# CPS.net
KiCad netlist of a schematic drawn in Altium Designer
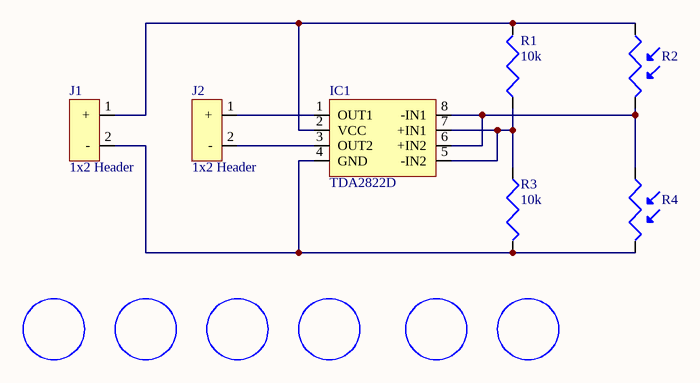
[diagram p0: CPS.SchDoc]

(export (version "E")
  (design (tool "Eeschema 10.0.6"))
  (components
    (comp (ref "H1") (value "Hole") (footprint "Hole") (libsource (lib "CPS") (part "Hole")))
    (comp (ref "H2") (value "Hole") (footprint "Hole") (libsource (lib "CPS") (part "Hole")))
    (comp (ref "H3") (value "Hole") (footprint "Hole") (libsource (lib "CPS") (part "Hole")))
    (comp (ref "H4") (value "Hole") (footprint "Hole") (libsource (lib "CPS") (part "Hole")))
    (comp (ref "H5") (value "Hole") (footprint "Hole") (libsource (lib "CPS") (part "Hole")))
    (comp (ref "H6") (value "Hole") (footprint "Hole") (libsource (lib "CPS") (part "Hole")))
    (comp (ref "IC1")
      (value "TDA2822D")
      (footprint "TDA2822D")
      (description "Audio Amp Headphone/Speaker 1-CH Mono/2-CH Stereo 1W Class-AB 8-Pin SO N Tube")
      (fields (field (name "MANUFACTURER") "STMicroelectronics"))
      (libsource (lib "CPS") (part "TDA2822D"))
    )
    (comp (ref "J1")
      (value "1x2 Header")
      (footprint "Conector")
      (description "KK 254 Wire-to-Board Header, Vertical, with Friction Lock, 2 Circuits, Gold (Au) Plating")
      (fields (field (name "MANUFACTURER") "Molex") (field (name "MANUFACTURER PART NUMBER") "22-29-2021"))
      (libsource (lib "CPS") (part "22-29-2021"))
    )
    (comp (ref "J2")
      (value "1x2 Header")
      (footprint "Conector")
      (description "KK 254 Wire-to-Board Header, Vertical, with Friction Lock, 2 Circuits, Gold (Au) Plating")
      (fields (field (name "MANUFACTURER") "Molex") (field (name "MANUFACTURER PART NUMBER") "22-29-2021"))
      (libsource (lib "CPS") (part "22-29-2021"))
    )
    (comp (ref "R1")
      (value "10k")
      (footprint "R0603")
      (description "SMD Chip Resistor, 10 kOhm, ± 1%, 100 mW, 0603 [1608 Metric], Thick Film, General Purpose")
      (fields
        (field (name "MANUFACTURER") "Vishay")
        (field (name "MANUFACTURER PART NUMBER") "CRCW060310K0FKEA")
      )
      (libsource (lib "CPS") (part "CRCW060310K0FKEA"))
    )
    (comp (ref "R2")
      (value "500k")
      (footprint "Photoresistor")
      (description "Ldr, 500 Kohm, 80MW, VT900 Series")
      (fields (field (name "MANUFACTURER") "Excelitas") (field (name "MANUFACTURER PART NUMBER") "VT90N2"))
      (libsource (lib "CPS") (part "VT90N2"))
    )
    (comp (ref "R3")
      (value "10k")
      (footprint "R0603")
      (description "SMD Chip Resistor, 10 kOhm, ± 1%, 100 mW, 0603 [1608 Metric], Thick Film, General Purpose")
      (fields
        (field (name "MANUFACTURER") "Vishay")
        (field (name "MANUFACTURER PART NUMBER") "CRCW060310K0FKEA")
      )
      (libsource (lib "CPS") (part "CRCW060310K0FKEA"))
    )
    (comp (ref "R4")
      (value "500k")
      (footprint "Photoresistor")
      (description "Ldr, 500 Kohm, 80MW, VT900 Series")
      (fields (field (name "MANUFACTURER") "Excelitas") (field (name "MANUFACTURER PART NUMBER") "VT90N2"))
      (libsource (lib "CPS") (part "VT90N2"))
    )
  )
  (nets
    (net (code "1") (name "Net-(IC1-+IN1)") (class "Default")
      (node (ref "IC1") (pin "5") (pinfunction "-IN2_5") (pintype "passive"))
      (node (ref "IC1") (pin "7") (pinfunction "+IN1_7") (pintype "passive"))
      (node (ref "R1") (pin "1") (pinfunction "1_1") (pintype "passive"))
      (node (ref "R3") (pin "1") (pinfunction "1_1") (pintype "passive"))
    )
    (net (code "2") (name "Net-(IC1-+IN2)") (class "Default")
      (node (ref "IC1") (pin "6") (pinfunction "+IN2_6") (pintype "passive"))
      (node (ref "IC1") (pin "8") (pinfunction "-IN1_8") (pintype "passive"))
      (node (ref "R2") (pin "2") (pinfunction "2_2") (pintype "passive"))
      (node (ref "R4") (pin "1") (pinfunction "1_1") (pintype "passive"))
    )
    (net (code "3") (name "Net-(IC1-GND)") (class "Default")
      (node (ref "IC1") (pin "4") (pinfunction "GND_4") (pintype "passive"))
      (node (ref "J1") (pin "2") (pinfunction "-_2") (pintype "passive"))
      (node (ref "R3") (pin "2") (pinfunction "2_2") (pintype "passive"))
      (node (ref "R4") (pin "2") (pinfunction "2_2") (pintype "passive"))
    )
    (net (code "4") (name "Net-(IC1-OUT1)") (class "Default")
      (node (ref "IC1") (pin "1") (pinfunction "OUT1_1") (pintype "passive"))
      (node (ref "J2") (pin "1") (pinfunction "+_1") (pintype "passive"))
    )
    (net (code "5") (name "Net-(IC1-OUT2)") (class "Default")
      (node (ref "IC1") (pin "3") (pinfunction "OUT2_3") (pintype "passive"))
      (node (ref "J2") (pin "2") (pinfunction "-_2") (pintype "passive"))
    )
    (net (code "6") (name "Net-(IC1-VCC)") (class "Default")
      (node (ref "IC1") (pin "2") (pinfunction "VCC_2") (pintype "passive"))
      (node (ref "J1") (pin "1") (pinfunction "+_1") (pintype "passive"))
      (node (ref "R1") (pin "2") (pinfunction "2_2") (pintype "passive"))
      (node (ref "R2") (pin "1") (pinfunction "1_1") (pintype "passive"))
    )
  )
)
